# 20190505.net
KiCad netlist of a schematic drawn in EAGLE
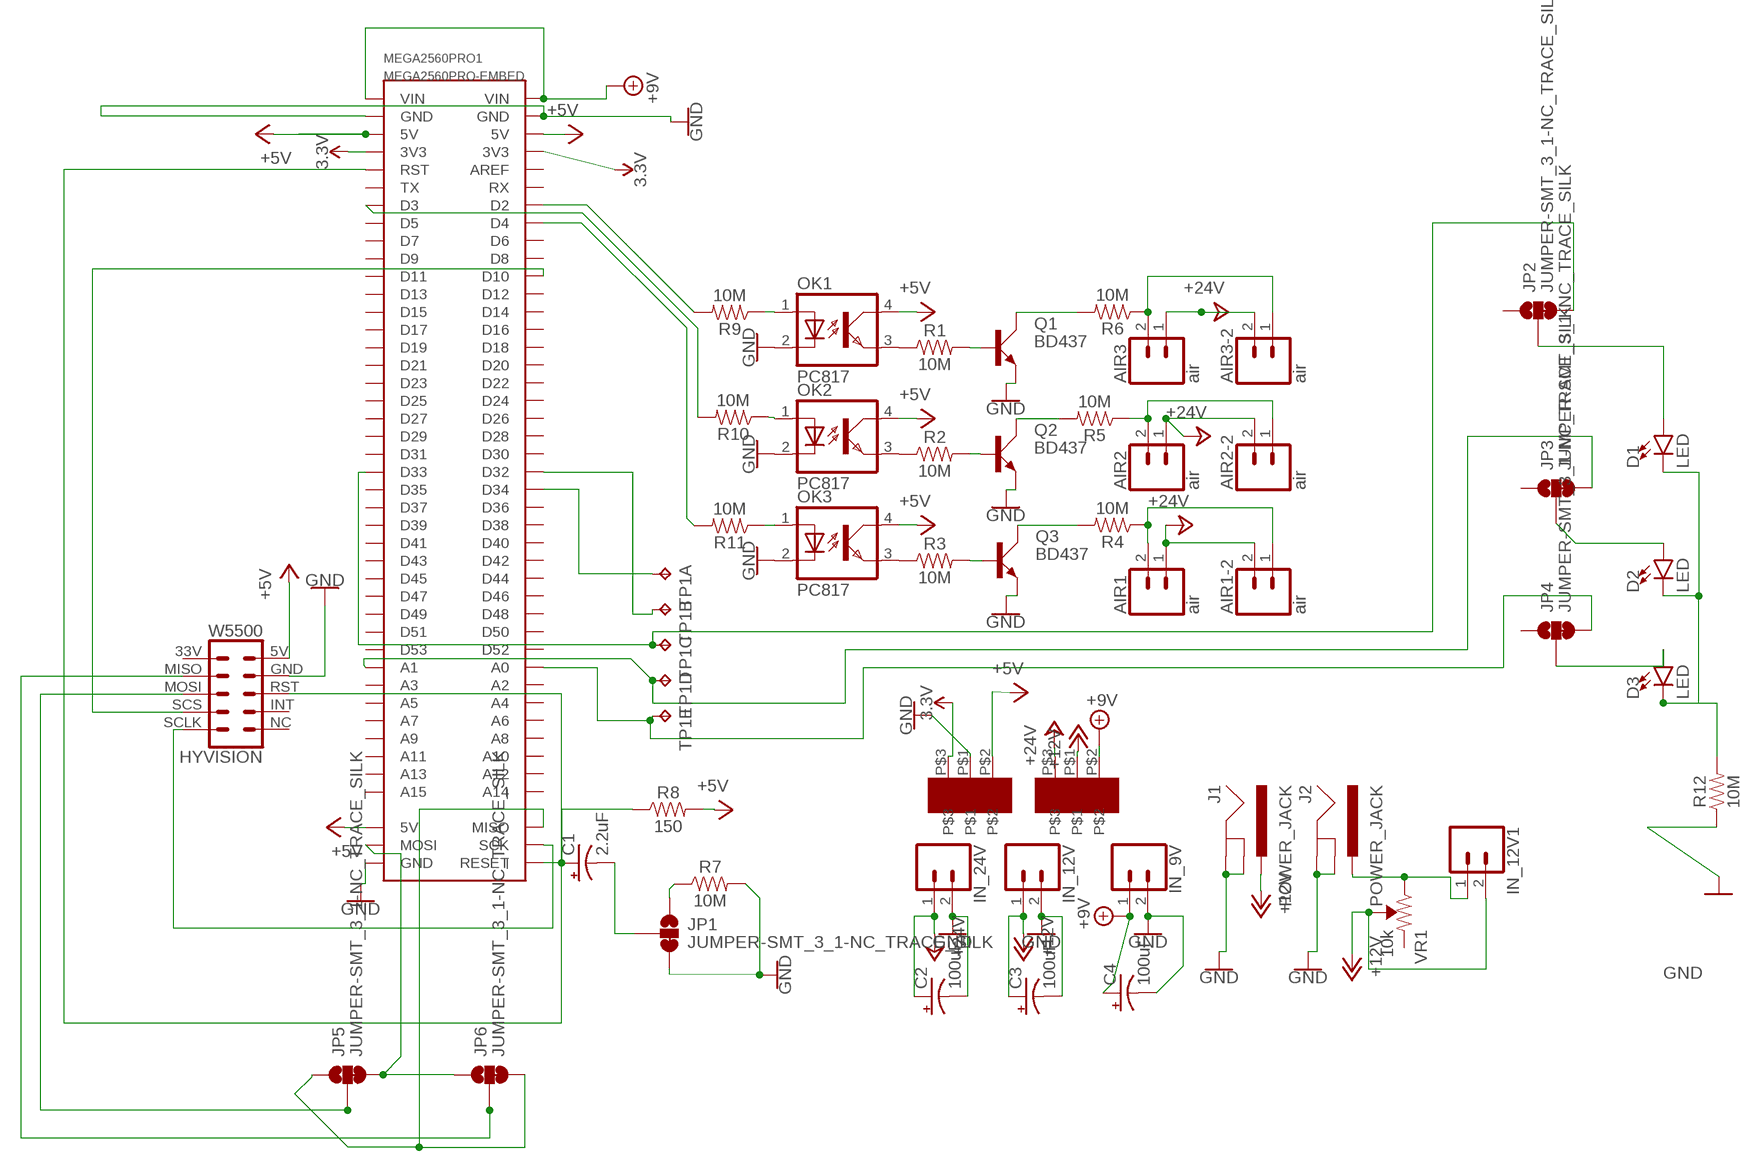
[diagram p0: schematic, sheet 1]

(export (version "E")
  (design (tool "Eeschema 10.0.6"))
  (components
    (comp (ref "AIR1")
      (value "air")
      (footprint "eagle-import:MOLEX-1X2_LOCK")
      (libsource (lib "eagle-import") (part "CONN_02POLAR_LOCK"))
    )
    (comp (ref "AIR1-2")
      (value "air")
      (footprint "eagle-import:1X02")
      (libsource (lib "eagle-import") (part "CONN_02"))
    )
    (comp (ref "AIR2")
      (value "air")
      (footprint "eagle-import:MOLEX-1X2_LOCK")
      (libsource (lib "eagle-import") (part "CONN_02POLAR_LOCK"))
    )
    (comp (ref "AIR2-2")
      (value "air")
      (footprint "eagle-import:1X02")
      (libsource (lib "eagle-import") (part "CONN_02"))
    )
    (comp (ref "AIR3")
      (value "air")
      (footprint "eagle-import:MOLEX-1X2_LOCK")
      (libsource (lib "eagle-import") (part "CONN_02POLAR_LOCK"))
    )
    (comp (ref "AIR3-2")
      (value "air")
      (footprint "eagle-import:1X02")
      (libsource (lib "eagle-import") (part "CONN_02"))
    )
    (comp (ref "C1")
      (value "2.2uF")
      (footprint "eagle-import:CPOL-RADIAL-2.5MM-5MM-KIT")
      (libsource (lib "eagle-import") (part "10UF-POLAR-RADIAL-2.5MM-KIT-25V-20%"))
    )
    (comp (ref "C2")
      (value "100uF")
      (footprint "eagle-import:CPOL-RADIAL-2.5MM-6.5MM")
      (libsource (lib "eagle-import") (part "100UF-POLAR-RADIAL-2.5MM-25V-20%"))
    )
    (comp (ref "C3")
      (value "100uF")
      (footprint "eagle-import:CPOL-RADIAL-2.5MM-6.5MM")
      (libsource (lib "eagle-import") (part "100UF-POLAR-RADIAL-2.5MM-25V-20%"))
    )
    (comp (ref "C4")
      (value "100uF")
      (footprint "eagle-import:CPOL-RADIAL-2.5MM-6.5MM")
      (libsource (lib "eagle-import") (part "100UF-POLAR-RADIAL-2.5MM-25V-20%"))
    )
    (comp (ref "D1")
      (value "LED")
      (footprint "eagle-import:LED_5MM")
      (libsource (lib "eagle-import") (part "LED5MM"))
    )
    (comp (ref "D2")
      (value "LED")
      (footprint "eagle-import:LED_5MM")
      (libsource (lib "eagle-import") (part "LED5MM"))
    )
    (comp (ref "D3")
      (value "LED")
      (footprint "eagle-import:LED_5MM")
      (libsource (lib "eagle-import") (part "LED5MM"))
    )
    (comp (ref "HYVISION")
      (value "W5500")
      (footprint "eagle-import:W5500")
      (libsource (lib "eagle-import") (part "W5500"))
    )
    (comp (ref "IN_9V")
      (value "CONN_02POLAR_LOCK")
      (footprint "eagle-import:MOLEX-1X2_LOCK")
      (libsource (lib "eagle-import") (part "CONN_02POLAR_LOCK"))
    )
    (comp (ref "IN_12V")
      (value "CONN_02POLAR_LOCK")
      (footprint "eagle-import:MOLEX-1X2_LOCK")
      (libsource (lib "eagle-import") (part "CONN_02POLAR_LOCK"))
    )
    (comp (ref "IN_12V1")
      (value "CONN_02POLAR_LOCK")
      (footprint "eagle-import:MOLEX-1X2_LOCK")
      (libsource (lib "eagle-import") (part "CONN_02POLAR_LOCK"))
    )
    (comp (ref "IN_24V")
      (value "CONN_02POLAR_LOCK")
      (footprint "eagle-import:MOLEX-1X2_LOCK")
      (libsource (lib "eagle-import") (part "CONN_02POLAR_LOCK"))
    )
    (comp (ref "J1")
      (value "POWER_JACK")
      (footprint "eagle-import:POWER_JACK_PTH")
      (libsource (lib "eagle-import") (part "POWER_JACK"))
    )
    (comp (ref "J2")
      (value "POWER_JACK")
      (footprint "eagle-import:POWER_JACK_PTH")
      (libsource (lib "eagle-import") (part "POWER_JACK"))
    )
    (comp (ref "JP1")
      (value "JUMPER-SMT_3_1-NC_TRACE_SILK")
      (footprint "eagle-import:SMT-JUMPER_3_1-NC_TRACE_SILK")
      (libsource (lib "eagle-import") (part "JUMPER-SMT_3_1-NC_TRACE_SILK"))
    )
    (comp (ref "JP2")
      (value "JUMPER-SMT_3_1-NC_TRACE_SILK")
      (footprint "eagle-import:SMT-JUMPER_3_1-NC_TRACE_SILK")
      (libsource (lib "eagle-import") (part "JUMPER-SMT_3_1-NC_TRACE_SILK"))
    )
    (comp (ref "JP3")
      (value "JUMPER-SMT_3_1-NC_TRACE_SILK")
      (footprint "eagle-import:SMT-JUMPER_3_1-NC_TRACE_SILK")
      (libsource (lib "eagle-import") (part "JUMPER-SMT_3_1-NC_TRACE_SILK"))
    )
    (comp (ref "JP4")
      (value "JUMPER-SMT_3_1-NC_TRACE_SILK")
      (footprint "eagle-import:SMT-JUMPER_3_1-NC_TRACE_SILK")
      (libsource (lib "eagle-import") (part "JUMPER-SMT_3_1-NC_TRACE_SILK"))
    )
    (comp (ref "JP5")
      (value "JUMPER-SMT_3_1-NC_TRACE_SILK")
      (footprint "eagle-import:SMT-JUMPER_3_1-NC_TRACE_SILK")
      (libsource (lib "eagle-import") (part "JUMPER-SMT_3_1-NC_TRACE_SILK"))
    )
    (comp (ref "JP6")
      (value "JUMPER-SMT_3_1-NC_TRACE_SILK")
      (footprint "eagle-import:SMT-JUMPER_3_1-NC_TRACE_SILK")
      (libsource (lib "eagle-import") (part "JUMPER-SMT_3_1-NC_TRACE_SILK"))
    )
    (comp (ref "MEGA2560PRO1")
      (value "MEGA2560PRO-EMBED")
      (footprint "eagle-import:MEGA2560PRO-EMBED")
      (libsource (lib "eagle-import") (part "MEGA2560PRO-EMBED"))
    )
    (comp (ref "OK1")
      (value "PC817")
      (footprint "eagle-import:DIL04")
      (fields (field (name "MPN") "PC817X4J000F"))
      (libsource (lib "eagle-import") (part "PC817"))
    )
    (comp (ref "OK2")
      (value "PC817")
      (footprint "eagle-import:DIL04")
      (fields (field (name "MPN") "PC817X4J000F"))
      (libsource (lib "eagle-import") (part "PC817"))
    )
    (comp (ref "OK3")
      (value "PC817")
      (footprint "eagle-import:DIL04")
      (fields (field (name "MPN") "PC817X4J000F"))
      (libsource (lib "eagle-import") (part "PC817"))
    )
    (comp (ref "Q1")
      (value "BD437")
      (footprint "eagle-import:TO126AV")
      (libsource (lib "eagle-import") (part "BD437"))
    )
    (comp (ref "Q2")
      (value "BD437")
      (footprint "eagle-import:TO126AV")
      (libsource (lib "eagle-import") (part "BD437"))
    )
    (comp (ref "Q3")
      (value "BD437")
      (footprint "eagle-import:TO126AV")
      (libsource (lib "eagle-import") (part "BD437"))
    )
    (comp (ref "R1")
      (value "10M")
      (footprint "eagle-import:AXIAL-0.3")
      (libsource (lib "eagle-import") (part "10MOHM-HORIZ-1/4W-5%"))
    )
    (comp (ref "R2")
      (value "10M")
      (footprint "eagle-import:AXIAL-0.3")
      (libsource (lib "eagle-import") (part "10MOHM-HORIZ-1/4W-5%"))
    )
    (comp (ref "R3")
      (value "10M")
      (footprint "eagle-import:AXIAL-0.3")
      (libsource (lib "eagle-import") (part "10MOHM-HORIZ-1/4W-5%"))
    )
    (comp (ref "R4")
      (value "10M")
      (footprint "eagle-import:AXIAL-0.3")
      (libsource (lib "eagle-import") (part "10MOHM-HORIZ-1/4W-5%"))
    )
    (comp (ref "R5")
      (value "10M")
      (footprint "eagle-import:AXIAL-0.3")
      (libsource (lib "eagle-import") (part "10MOHM-HORIZ-1/4W-5%"))
    )
    (comp (ref "R6")
      (value "10M")
      (footprint "eagle-import:AXIAL-0.3")
      (libsource (lib "eagle-import") (part "10MOHM-HORIZ-1/4W-5%"))
    )
    (comp (ref "R7")
      (value "10M")
      (footprint "eagle-import:AXIAL-0.3")
      (libsource (lib "eagle-import") (part "10MOHM-HORIZ-1/4W-5%"))
    )
    (comp (ref "R8")
      (value "150")
      (footprint "eagle-import:AXIAL-0.3")
      (libsource (lib "eagle-import") (part "10MOHM-HORIZ-1/4W-5%"))
    )
    (comp (ref "R9")
      (value "10M")
      (footprint "eagle-import:AXIAL-0.3")
      (libsource (lib "eagle-import") (part "10MOHM-HORIZ-1/4W-5%"))
    )
    (comp (ref "R10")
      (value "10M")
      (footprint "eagle-import:AXIAL-0.3")
      (libsource (lib "eagle-import") (part "10MOHM-HORIZ-1/4W-5%"))
    )
    (comp (ref "R11")
      (value "10M")
      (footprint "eagle-import:AXIAL-0.3")
      (libsource (lib "eagle-import") (part "10MOHM-HORIZ-1/4W-5%"))
    )
    (comp (ref "R12")
      (value "10M")
      (footprint "eagle-import:AXIAL-0.3")
      (libsource (lib "eagle-import") (part "10MOHM-HORIZ-1/4W-5%"))
    )
    (comp (ref "TP1")
      (value "TP5P5-25-13")
      (footprint "eagle-import:P5-25-13")
      (libsource (lib "eagle-import") (part "TP5P5-25-13"))
    )
    (comp (ref "U$2")
      (value "AC_3PINAC3PIN7MM")
      (footprint "eagle-import:AC3PIN7MM")
      (libsource (lib "eagle-import") (part "AC_3PINAC3PIN7MM"))
    )
    (comp (ref "U$4")
      (value "AC_3PINAC3PIN7MM")
      (footprint "eagle-import:AC3PIN7MM")
      (libsource (lib "eagle-import") (part "AC_3PINAC3PIN7MM"))
    )
    (comp (ref "VR1")
      (value "10k")
      (footprint "eagle-import:TRIMPOT-PTH-3386U")
      (libsource (lib "eagle-import") (part "TRIMPOT-PTH-10MM-KNOB-1/2W-10%"))
    )
  )
  (nets
    (net (code "1") (name "+5V") (class "Default")
      (node (ref "HYVISION") (pin "5V") (pinfunction "5V_5V") (pintype "passive"))
      (node (ref "MEGA2560PRO1") (pin "5V@1") (pinfunction "5V_5V@1") (pintype "bidirectional"))
      (node (ref "MEGA2560PRO1") (pin "5V@2") (pinfunction "5V_5V@2") (pintype "bidirectional"))
      (node (ref "MEGA2560PRO1") (pin "5V@3") (pinfunction "5V_5V@3") (pintype "bidirectional"))
      (node (ref "OK1") (pin "4") (pinfunction "COL_4") (pintype "passive"))
      (node (ref "OK2") (pin "4") (pinfunction "COL_4") (pintype "passive"))
      (node (ref "OK3") (pin "4") (pinfunction "COL_4") (pintype "passive"))
      (node (ref "R8") (pin "P$2") (pinfunction "2_P$2") (pintype "passive"))
      (node (ref "U$4") (pin "P$2") (pinfunction "P$2_P$2") (pintype "bidirectional"))
    )
    (net (code "2") (name "+9V") (class "Default")
      (node (ref "C4") (pin "1") (pinfunction "+_1") (pintype "passive"))
      (node (ref "IN_9V") (pin "1") (pinfunction "1_1") (pintype "passive"))
      (node (ref "MEGA2560PRO1") (pin "VIN@1") (pinfunction "VIN_VIN@1") (pintype "bidirectional"))
      (node (ref "MEGA2560PRO1") (pin "VIN@2") (pinfunction "VIN_VIN@2") (pintype "bidirectional"))
      (node (ref "U$2") (pin "P$2") (pinfunction "P$2_P$2") (pintype "bidirectional"))
    )
    (net (code "3") (name "+12V") (class "Default")
      (node (ref "C3") (pin "1") (pinfunction "+_1") (pintype "passive"))
      (node (ref "IN_12V") (pin "1") (pinfunction "1_1") (pintype "passive"))
      (node (ref "IN_12V1") (pin "2") (pinfunction "2_2") (pintype "passive"))
      (node (ref "J1") (pin "PWR") (pinfunction "PWR_PWR") (pintype "bidirectional"))
      (node (ref "U$2") (pin "P$1") (pinfunction "P$1_P$1") (pintype "bidirectional"))
      (node (ref "VR1") (pin "2") (pinfunction "WIPER_2") (pintype "passive"))
    )
    (net (code "4") (name "+24V") (class "Default")
      (node (ref "AIR1") (pin "1") (pinfunction "1_1") (pintype "passive"))
      (node (ref "AIR1-2") (pin "2") (pinfunction "2_2") (pintype "passive"))
      (node (ref "AIR2") (pin "1") (pinfunction "1_1") (pintype "passive"))
      (node (ref "AIR2-2") (pin "2") (pinfunction "2_2") (pintype "passive"))
      (node (ref "AIR3") (pin "1") (pinfunction "1_1") (pintype "passive"))
      (node (ref "AIR3-2") (pin "2") (pinfunction "2_2") (pintype "passive"))
      (node (ref "C2") (pin "1") (pinfunction "+_1") (pintype "passive"))
      (node (ref "IN_24V") (pin "1") (pinfunction "1_1") (pintype "passive"))
      (node (ref "U$2") (pin "P$3") (pinfunction "P$3_P$3") (pintype "bidirectional"))
    )
    (net (code "5") (name "3.3V") (class "Default")
      (node (ref "MEGA2560PRO1") (pin "3V3@1") (pinfunction "3V3_3V3@1") (pintype "bidirectional"))
      (node (ref "MEGA2560PRO1") (pin "3V3@2") (pinfunction "3V3_3V3@2") (pintype "bidirectional"))
      (node (ref "U$4") (pin "P$3") (pinfunction "P$3_P$3") (pintype "bidirectional"))
    )
    (net (code "6") (name "GND") (class "Default")
      (node (ref "C2") (pin "2") (pinfunction "-_2") (pintype "passive"))
      (node (ref "C3") (pin "2") (pinfunction "-_2") (pintype "passive"))
      (node (ref "C4") (pin "2") (pinfunction "-_2") (pintype "passive"))
      (node (ref "HYVISION") (pin "GND") (pinfunction "GND_GND") (pintype "passive"))
      (node (ref "IN_12V") (pin "2") (pinfunction "2_2") (pintype "passive"))
      (node (ref "IN_24V") (pin "2") (pinfunction "2_2") (pintype "passive"))
      (node (ref "IN_9V") (pin "2") (pinfunction "2_2") (pintype "passive"))
      (node (ref "J1") (pin "GND") (pinfunction "GND_GND") (pintype "bidirectional"))
      (node (ref "J1") (pin "GNDBREAK") (pinfunction "GNDBREAK_GNDBREAK") (pintype "bidirectional"))
      (node (ref "J2") (pin "GND") (pinfunction "GND_GND") (pintype "bidirectional"))
      (node (ref "J2") (pin "GNDBREAK") (pinfunction "GNDBREAK_GNDBREAK") (pintype "bidirectional"))
      (node (ref "JP1") (pin "3") (pinfunction "3_3") (pintype "passive"))
      (node (ref "MEGA2560PRO1") (pin "GND@1") (pinfunction "GND_GND@1") (pintype "bidirectional"))
      (node (ref "MEGA2560PRO1") (pin "GND@2") (pinfunction "GND_GND@2") (pintype "bidirectional"))
      (node (ref "MEGA2560PRO1") (pin "GND@3") (pinfunction "GND_GND@3") (pintype "bidirectional"))
      (node (ref "OK1") (pin "2") (pinfunction "C_2") (pintype "passive"))
      (node (ref "OK2") (pin "2") (pinfunction "C_2") (pintype "passive"))
      (node (ref "OK3") (pin "2") (pinfunction "C_2") (pintype "passive"))
      (node (ref "Q1") (pin "E") (pinfunction "E_E") (pintype "passive"))
      (node (ref "Q2") (pin "E") (pinfunction "E_E") (pintype "passive"))
      (node (ref "Q3") (pin "E") (pinfunction "E_E") (pintype "passive"))
      (node (ref "R12") (pin "P$1") (pinfunction "1_P$1") (pintype "passive"))
      (node (ref "R7") (pin "P$2") (pinfunction "2_P$2") (pintype "passive"))
      (node (ref "U$4") (pin "P$1") (pinfunction "P$1_P$1") (pintype "bidirectional"))
    )
    (net (code "7") (name "Net-(C1-+)") (class "Default")
      (node (ref "C1") (pin "1") (pinfunction "+_1") (pintype "passive"))
      (node (ref "HYVISION") (pin "RST") (pinfunction "RST_RST") (pintype "passive"))
      (node (ref "MEGA2560PRO1") (pin "RESET") (pinfunction "RESET_RESET") (pintype "bidirectional"))
      (node (ref "MEGA2560PRO1") (pin "RST") (pinfunction "RST_RST") (pintype "bidirectional"))
      (node (ref "R8") (pin "P$1") (pinfunction "1_P$1") (pintype "passive"))
    )
    (net (code "8") (name "Net-(C1--)") (class "Default")
      (node (ref "C1") (pin "2") (pinfunction "-_2") (pintype "passive"))
      (node (ref "JP1") (pin "2") (pinfunction "2_2") (pintype "passive"))
    )
    (net (code "9") (name "Net-(D1-C)") (class "Default")
      (node (ref "D1") (pin "K") (pinfunction "C_K") (pintype "passive"))
      (node (ref "D2") (pin "K") (pinfunction "C_K") (pintype "passive"))
      (node (ref "D3") (pin "K") (pinfunction "C_K") (pintype "passive"))
      (node (ref "R12") (pin "P$2") (pinfunction "2_P$2") (pintype "passive"))
    )
    (net (code "10") (name "Net-(D1-PadA)") (class "Default")
      (node (ref "D1") (pin "A") (pinfunction "A_A") (pintype "passive"))
      (node (ref "JP2") (pin "2") (pinfunction "2_2") (pintype "passive"))
    )
    (net (code "11") (name "Net-(D2-PadA)") (class "Default")
      (node (ref "D2") (pin "A") (pinfunction "A_A") (pintype "passive"))
      (node (ref "JP3") (pin "2") (pinfunction "2_2") (pintype "passive"))
    )
    (net (code "12") (name "Net-(D3-PadA)") (class "Default")
      (node (ref "D3") (pin "A") (pinfunction "A_A") (pintype "passive"))
      (node (ref "JP4") (pin "2") (pinfunction "2_2") (pintype "passive"))
    )
    (net (code "13") (name "Net-(HYVISION-PadMISO)") (class "Default")
      (node (ref "HYVISION") (pin "MISO") (pinfunction "MISO_MISO") (pintype "passive"))
      (node (ref "JP6") (pin "2") (pinfunction "2_2") (pintype "passive"))
    )
    (net (code "14") (name "Net-(HYVISION-PadMOSI)") (class "Default")
      (node (ref "HYVISION") (pin "MOSI") (pinfunction "MOSI_MOSI") (pintype "passive"))
      (node (ref "JP5") (pin "2") (pinfunction "2_2") (pintype "passive"))
    )
    (net (code "15") (name "Net-(HYVISION-PadSCLK)") (class "Default")
      (node (ref "HYVISION") (pin "SCLK") (pinfunction "SCLK_SCLK") (pintype "passive"))
      (node (ref "MEGA2560PRO1") (pin "SCK") (pinfunction "SCK_SCK") (pintype "bidirectional"))
    )
    (net (code "16") (name "Net-(HYVISION-PadSCS)") (class "Default")
      (node (ref "HYVISION") (pin "SCS") (pinfunction "SCS_SCS") (pintype "passive"))
      (node (ref "MEGA2560PRO1") (pin "D10") (pinfunction "D10_D10") (pintype "bidirectional"))
    )
    (net (code "17") (name "Net-(JP5-Pad1)") (class "Default")
      (node (ref "JP5") (pin "1") (pinfunction "1_1") (pintype "passive"))
      (node (ref "JP6") (pin "3") (pinfunction "3_3") (pintype "passive"))
      (node (ref "MEGA2560PRO1") (pin "MISO") (pinfunction "MISO_MISO") (pintype "bidirectional"))
    )
    (net (code "18") (name "Net-(JP5-Pad3)") (class "Default")
      (node (ref "JP5") (pin "3") (pinfunction "3_3") (pintype "passive"))
      (node (ref "JP6") (pin "1") (pinfunction "1_1") (pintype "passive"))
      (node (ref "MEGA2560PRO1") (pin "MOSI") (pinfunction "MOSI_MOSI") (pintype "bidirectional"))
    )
    (net (code "19") (name "Net-(OK1-A)") (class "Default")
      (node (ref "OK1") (pin "1") (pinfunction "A_1") (pintype "passive"))
      (node (ref "R9") (pin "P$1") (pinfunction "1_P$1") (pintype "passive"))
    )
    (net (code "20") (name "Net-(OK1-EMIT)") (class "Default")
      (node (ref "OK1") (pin "3") (pinfunction "EMIT_3") (pintype "passive"))
      (node (ref "R1") (pin "P$1") (pinfunction "1_P$1") (pintype "passive"))
    )
    (net (code "21") (name "Net-(OK2-A)") (class "Default")
      (node (ref "OK2") (pin "1") (pinfunction "A_1") (pintype "passive"))
      (node (ref "R10") (pin "P$1") (pinfunction "1_P$1") (pintype "passive"))
    )
    (net (code "22") (name "Net-(OK2-EMIT)") (class "Default")
      (node (ref "OK2") (pin "3") (pinfunction "EMIT_3") (pintype "passive"))
      (node (ref "R2") (pin "P$1") (pinfunction "1_P$1") (pintype "passive"))
    )
    (net (code "23") (name "Net-(OK3-A)") (class "Default")
      (node (ref "OK3") (pin "1") (pinfunction "A_1") (pintype "passive"))
      (node (ref "R11") (pin "P$1") (pinfunction "1_P$1") (pintype "passive"))
    )
    (net (code "24") (name "Net-(OK3-EMIT)") (class "Default")
      (node (ref "OK3") (pin "3") (pinfunction "EMIT_3") (pintype "passive"))
      (node (ref "R3") (pin "P$1") (pinfunction "1_P$1") (pintype "passive"))
    )
    (net (code "25") (name "Net-(R1-2)") (class "Default")
      (node (ref "Q1") (pin "B") (pinfunction "B_B") (pintype "passive"))
      (node (ref "R1") (pin "P$2") (pinfunction "2_P$2") (pintype "passive"))
    )
    (net (code "26") (name "Net-(R2-2)") (class "Default")
      (node (ref "Q2") (pin "B") (pinfunction "B_B") (pintype "passive"))
      (node (ref "R2") (pin "P$2") (pinfunction "2_P$2") (pintype "passive"))
    )
    (net (code "27") (name "Net-(R3-2)") (class "Default")
      (node (ref "Q3") (pin "B") (pinfunction "B_B") (pintype "passive"))
      (node (ref "R3") (pin "P$2") (pinfunction "2_P$2") (pintype "passive"))
    )
    (net (code "28") (name "Net-(R4-1)") (class "Default")
      (node (ref "AIR1") (pin "2") (pinfunction "2_2") (pintype "passive"))
      (node (ref "AIR1-2") (pin "1") (pinfunction "1_1") (pintype "passive"))
      (node (ref "R4") (pin "P$1") (pinfunction "1_P$1") (pintype "passive"))
    )
    (net (code "29") (name "Net-(R4-2)") (class "Default")
      (node (ref "Q3") (pin "C") (pinfunction "C_C") (pintype "passive"))
      (node (ref "R4") (pin "P$2") (pinfunction "2_P$2") (pintype "passive"))
    )
    (net (code "30") (name "Net-(R5-1)") (class "Default")
      (node (ref "AIR2") (pin "2") (pinfunction "2_2") (pintype "passive"))
      (node (ref "AIR2-2") (pin "1") (pinfunction "1_1") (pintype "passive"))
      (node (ref "R5") (pin "P$1") (pinfunction "1_P$1") (pintype "passive"))
    )
    (net (code "31") (name "Net-(R5-2)") (class "Default")
      (node (ref "Q2") (pin "C") (pinfunction "C_C") (pintype "passive"))
      (node (ref "R5") (pin "P$2") (pinfunction "2_P$2") (pintype "passive"))
    )
    (net (code "32") (name "Net-(R6-1)") (class "Default")
      (node (ref "AIR3") (pin "2") (pinfunction "2_2") (pintype "passive"))
      (node (ref "AIR3-2") (pin "1") (pinfunction "1_1") (pintype "passive"))
      (node (ref "R6") (pin "P$1") (pinfunction "1_P$1") (pintype "passive"))
    )
    (net (code "33") (name "Net-(R6-2)") (class "Default")
      (node (ref "Q1") (pin "C") (pinfunction "C_C") (pintype "passive"))
      (node (ref "R6") (pin "P$2") (pinfunction "2_P$2") (pintype "passive"))
    )
    (net (code "34") (name "Net-(R7-1)") (class "Default")
      (node (ref "JP1") (pin "1") (pinfunction "1_1") (pintype "passive"))
      (node (ref "R7") (pin "P$1") (pinfunction "1_P$1") (pintype "passive"))
    )
    (net (code "35") (name "Net-(R9-2)") (class "Default")
      (node (ref "MEGA2560PRO1") (pin "D2") (pinfunction "D2_D2") (pintype "bidirectional"))
      (node (ref "R9") (pin "P$2") (pinfunction "2_P$2") (pintype "passive"))
    )
    (net (code "36") (name "Net-(R10-2)") (class "Default")
      (node (ref "MEGA2560PRO1") (pin "D3") (pinfunction "D3_D3") (pintype "bidirectional"))
      (node (ref "R10") (pin "P$2") (pinfunction "2_P$2") (pintype "passive"))
    )
    (net (code "37") (name "Net-(R11-2)") (class "Default")
      (node (ref "MEGA2560PRO1") (pin "D4") (pinfunction "D4_D4") (pintype "bidirectional"))
      (node (ref "R11") (pin "P$2") (pinfunction "2_P$2") (pintype "passive"))
    )
    (net (code "38") (name "Net-(TP1A-TP)") (class "Default")
      (node (ref "MEGA2560PRO1") (pin "D34") (pinfunction "D34_D34") (pintype "bidirectional"))
      (node (ref "TP1") (pin "TP-1") (pinfunction "TP_TP-1") (pintype "input"))
    )
    (net (code "39") (name "Net-(TP1B-TP)") (class "Default")
      (node (ref "MEGA2560PRO1") (pin "D32") (pinfunction "D32_D32") (pintype "bidirectional"))
      (node (ref "TP1") (pin "TP-2") (pinfunction "TP_TP-2") (pintype "input"))
    )
    (net (code "40") (name "Net-(TP1C-TP)") (class "Default")
      (node (ref "JP2") (pin "3") (pinfunction "3_3") (pintype "passive"))
      (node (ref "MEGA2560PRO1") (pin "D33") (pinfunction "D33_D33") (pintype "bidirectional"))
      (node (ref "TP1") (pin "TP-3") (pinfunction "TP_TP-3") (pintype "input"))
    )
    (net (code "41") (name "Net-(TP1D-TP)") (class "Default")
      (node (ref "JP3") (pin "3") (pinfunction "3_3") (pintype "passive"))
      (node (ref "MEGA2560PRO1") (pin "A1") (pinfunction "A1_A1") (pintype "bidirectional"))
      (node (ref "TP1") (pin "TP-4") (pinfunction "TP_TP-4") (pintype "input"))
    )
    (net (code "42") (name "Net-(TP1E-TP)") (class "Default")
      (node (ref "JP4") (pin "3") (pinfunction "3_3") (pintype "passive"))
      (node (ref "MEGA2560PRO1") (pin "A0") (pinfunction "A0_A0") (pintype "bidirectional"))
      (node (ref "TP1") (pin "TP-5") (pinfunction "TP_TP-5") (pintype "input"))
    )
    (net (code "43") (name "Net-(VR1-CW)") (class "Default")
      (node (ref "IN_12V1") (pin "1") (pinfunction "1_1") (pintype "passive"))
      (node (ref "J2") (pin "PWR") (pinfunction "PWR_PWR") (pintype "bidirectional"))
      (node (ref "VR1") (pin "3") (pinfunction "CW_3") (pintype "passive"))
    )
    (net (code "44") (name "unconnected-(HYVISION-3V3-Pad33V)") (class "Default")
      (node (ref "HYVISION") (pin "33V") (pinfunction "3V3_33V") (pintype "passive"))
    )
    (net (code "45") (name "unconnected-(HYVISION-PadINT)") (class "Default")
      (node (ref "HYVISION") (pin "INT") (pinfunction "INT_INT") (pintype "passive"))
    )
    (net (code "46") (name "unconnected-(HYVISION-PadNC)") (class "Default")
      (node (ref "HYVISION") (pin "NC") (pinfunction "NC_NC") (pintype "passive"))
    )
    (net (code "47") (name "unconnected-(JP2-Pad1)") (class "Default")
      (node (ref "JP2") (pin "1") (pinfunction "1_1") (pintype "passive"))
    )
    (net (code "48") (name "unconnected-(JP3-Pad1)") (class "Default")
      (node (ref "JP3") (pin "1") (pinfunction "1_1") (pintype "passive"))
    )
    (net (code "49") (name "unconnected-(JP4-Pad1)") (class "Default")
      (node (ref "JP4") (pin "1") (pinfunction "1_1") (pintype "passive"))
    )
    (net (code "50") (name "unconnected-(MEGA2560PRO1-PadA2)") (class "Default")
      (node (ref "MEGA2560PRO1") (pin "A2") (pinfunction "A2_A2") (pintype "bidirectional"))
    )
    (net (code "51") (name "unconnected-(MEGA2560PRO1-PadA3)") (class "Default")
      (node (ref "MEGA2560PRO1") (pin "A3") (pinfunction "A3_A3") (pintype "bidirectional"))
    )
    (net (code "52") (name "unconnected-(MEGA2560PRO1-PadA4)") (class "Default")
      (node (ref "MEGA2560PRO1") (pin "A4") (pinfunction "A4_A4") (pintype "bidirectional"))
    )
    (net (code "53") (name "unconnected-(MEGA2560PRO1-PadA5)") (class "Default")
      (node (ref "MEGA2560PRO1") (pin "A5") (pinfunction "A5_A5") (pintype "bidirectional"))
    )
    (net (code "54") (name "unconnected-(MEGA2560PRO1-PadA6)") (class "Default")
      (node (ref "MEGA2560PRO1") (pin "A6") (pinfunction "A6_A6") (pintype "bidirectional"))
    )
    (net (code "55") (name "unconnected-(MEGA2560PRO1-PadA7)") (class "Default")
      (node (ref "MEGA2560PRO1") (pin "A7") (pinfunction "A7_A7") (pintype "bidirectional"))
    )
    (net (code "56") (name "unconnected-(MEGA2560PRO1-PadA8)") (class "Default")
      (node (ref "MEGA2560PRO1") (pin "A8") (pinfunction "A8_A8") (pintype "bidirectional"))
    )
    (net (code "57") (name "unconnected-(MEGA2560PRO1-PadA9)") (class "Default")
      (node (ref "MEGA2560PRO1") (pin "A9") (pinfunction "A9_A9") (pintype "bidirectional"))
    )
    (net (code "58") (name "unconnected-(MEGA2560PRO1-PadA10)") (class "Default")
      (node (ref "MEGA2560PRO1") (pin "A10") (pinfunction "A10_A10") (pintype "bidirectional"))
    )
    (net (code "59") (name "unconnected-(MEGA2560PRO1-PadA11)") (class "Default")
      (node (ref "MEGA2560PRO1") (pin "A11") (pinfunction "A11_A11") (pintype "bidirectional"))
    )
    (net (code "60") (name "unconnected-(MEGA2560PRO1-PadA12)") (class "Default")
      (node (ref "MEGA2560PRO1") (pin "A12") (pinfunction "A12_A12") (pintype "bidirectional"))
    )
    (net (code "61") (name "unconnected-(MEGA2560PRO1-PadA13)") (class "Default")
      (node (ref "MEGA2560PRO1") (pin "A13") (pinfunction "A13_A13") (pintype "bidirectional"))
    )
    (net (code "62") (name "unconnected-(MEGA2560PRO1-PadA14)") (class "Default")
      (node (ref "MEGA2560PRO1") (pin "A14") (pinfunction "A14_A14") (pintype "bidirectional"))
    )
    (net (code "63") (name "unconnected-(MEGA2560PRO1-PadA15)") (class "Default")
      (node (ref "MEGA2560PRO1") (pin "A15") (pinfunction "A15_A15") (pintype "bidirectional"))
    )
    (net (code "64") (name "unconnected-(MEGA2560PRO1-PadAREF)") (class "Default")
      (node (ref "MEGA2560PRO1") (pin "AREF") (pinfunction "AREF_AREF") (pintype "bidirectional"))
    )
    (net (code "65") (name "unconnected-(MEGA2560PRO1-PadD5)") (class "Default")
      (node (ref "MEGA2560PRO1") (pin "D5") (pinfunction "D5_D5") (pintype "bidirectional"))
    )
    (net (code "66") (name "unconnected-(MEGA2560PRO1-PadD6)") (class "Default")
      (node (ref "MEGA2560PRO1") (pin "D6") (pinfunction "D6_D6") (pintype "bidirectional"))
    )
    (net (code "67") (name "unconnected-(MEGA2560PRO1-PadD7)") (class "Default")
      (node (ref "MEGA2560PRO1") (pin "D7") (pinfunction "D7_D7") (pintype "bidirectional"))
    )
    (net (code "68") (name "unconnected-(MEGA2560PRO1-PadD8)") (class "Default")
      (node (ref "MEGA2560PRO1") (pin "D8") (pinfunction "D8_D8") (pintype "bidirectional"))
    )
    (net (code "69") (name "unconnected-(MEGA2560PRO1-PadD9)") (class "Default")
      (node (ref "MEGA2560PRO1") (pin "D9") (pinfunction "D9_D9") (pintype "bidirectional"))
    )
    (net (code "70") (name "unconnected-(MEGA2560PRO1-PadD11)") (class "Default")
      (node (ref "MEGA2560PRO1") (pin "D11") (pinfunction "D11_D11") (pintype "bidirectional"))
    )
    (net (code "71") (name "unconnected-(MEGA2560PRO1-PadD12)") (class "Default")
      (node (ref "MEGA2560PRO1") (pin "D12") (pinfunction "D12_D12") (pintype "bidirectional"))
    )
    (net (code "72") (name "unconnected-(MEGA2560PRO1-PadD13)") (class "Default")
      (node (ref "MEGA2560PRO1") (pin "D13") (pinfunction "D13_D13") (pintype "bidirectional"))
    )
    (net (code "73") (name "unconnected-(MEGA2560PRO1-PadD14)") (class "Default")
      (node (ref "MEGA2560PRO1") (pin "D14") (pinfunction "D14_D14") (pintype "bidirectional"))
    )
    (net (code "74") (name "unconnected-(MEGA2560PRO1-PadD15)") (class "Default")
      (node (ref "MEGA2560PRO1") (pin "D15") (pinfunction "D15_D15") (pintype "bidirectional"))
    )
    (net (code "75") (name "unconnected-(MEGA2560PRO1-PadD16)") (class "Default")
      (node (ref "MEGA2560PRO1") (pin "D16") (pinfunction "D16_D16") (pintype "bidirectional"))
    )
    (net (code "76") (name "unconnected-(MEGA2560PRO1-PadD17)") (class "Default")
      (node (ref "MEGA2560PRO1") (pin "D17") (pinfunction "D17_D17") (pintype "bidirectional"))
    )
    (net (code "77") (name "unconnected-(MEGA2560PRO1-PadD18)") (class "Default")
      (node (ref "MEGA2560PRO1") (pin "D18") (pinfunction "D18_D18") (pintype "bidirectional"))
    )
    (net (code "78") (name "unconnected-(MEGA2560PRO1-PadD19)") (class "Default")
      (node (ref "MEGA2560PRO1") (pin "D19") (pinfunction "D19_D19") (pintype "bidirectional"))
    )
    (net (code "79") (name "unconnected-(MEGA2560PRO1-PadD20)") (class "Default")
      (node (ref "MEGA2560PRO1") (pin "D20") (pinfunction "D20_D20") (pintype "bidirectional"))
    )
    (net (code "80") (name "unconnected-(MEGA2560PRO1-PadD21)") (class "Default")
      (node (ref "MEGA2560PRO1") (pin "D21") (pinfunction "D21_D21") (pintype "bidirectional"))
    )
    (net (code "81") (name "unconnected-(MEGA2560PRO1-PadD22)") (class "Default")
      (node (ref "MEGA2560PRO1") (pin "D22") (pinfunction "D22_D22") (pintype "bidirectional"))
    )
    (net (code "82") (name "unconnected-(MEGA2560PRO1-PadD23)") (class "Default")
      (node (ref "MEGA2560PRO1") (pin "D23") (pinfunction "D23_D23") (pintype "bidirectional"))
    )
    (net (code "83") (name "unconnected-(MEGA2560PRO1-PadD24)") (class "Default")
      (node (ref "MEGA2560PRO1") (pin "D24") (pinfunction "D24_D24") (pintype "bidirectional"))
    )
    (net (code "84") (name "unconnected-(MEGA2560PRO1-PadD25)") (class "Default")
      (node (ref "MEGA2560PRO1") (pin "D25") (pinfunction "D25_D25") (pintype "bidirectional"))
    )
    (net (code "85") (name "unconnected-(MEGA2560PRO1-PadD26)") (class "Default")
      (node (ref "MEGA2560PRO1") (pin "D26") (pinfunction "D26_D26") (pintype "bidirectional"))
    )
    (net (code "86") (name "unconnected-(MEGA2560PRO1-PadD27)") (class "Default")
      (node (ref "MEGA2560PRO1") (pin "D27") (pinfunction "D27_D27") (pintype "bidirectional"))
    )
    (net (code "87") (name "unconnected-(MEGA2560PRO1-PadD28)") (class "Default")
      (node (ref "MEGA2560PRO1") (pin "D28") (pinfunction "D28_D28") (pintype "bidirectional"))
    )
    (net (code "88") (name "unconnected-(MEGA2560PRO1-PadD29)") (class "Default")
      (node (ref "MEGA2560PRO1") (pin "D29") (pinfunction "D29_D29") (pintype "bidirectional"))
    )
    (net (code "89") (name "unconnected-(MEGA2560PRO1-PadD30)") (class "Default")
      (node (ref "MEGA2560PRO1") (pin "D30") (pinfunction "D30_D30") (pintype "bidirectional"))
    )
    (net (code "90") (name "unconnected-(MEGA2560PRO1-PadD31)") (class "Default")
      (node (ref "MEGA2560PRO1") (pin "D31") (pinfunction "D31_D31") (pintype "bidirectional"))
    )
    (net (code "91") (name "unconnected-(MEGA2560PRO1-PadD35)") (class "Default")
      (node (ref "MEGA2560PRO1") (pin "D35") (pinfunction "D35_D35") (pintype "bidirectional"))
    )
    (net (code "92") (name "unconnected-(MEGA2560PRO1-PadD36)") (class "Default")
      (node (ref "MEGA2560PRO1") (pin "D36") (pinfunction "D36_D36") (pintype "bidirectional"))
    )
    (net (code "93") (name "unconnected-(MEGA2560PRO1-PadD37)") (class "Default")
      (node (ref "MEGA2560PRO1") (pin "D37") (pinfunction "D37_D37") (pintype "bidirectional"))
    )
    (net (code "94") (name "unconnected-(MEGA2560PRO1-PadD38)") (class "Default")
      (node (ref "MEGA2560PRO1") (pin "D38") (pinfunction "D38_D38") (pintype "bidirectional"))
    )
    (net (code "95") (name "unconnected-(MEGA2560PRO1-PadD39)") (class "Default")
      (node (ref "MEGA2560PRO1") (pin "D39") (pinfunction "D39_D39") (pintype "bidirectional"))
    )
    (net (code "96") (name "unconnected-(MEGA2560PRO1-PadD40)") (class "Default")
      (node (ref "MEGA2560PRO1") (pin "D40") (pinfunction "D40_D40") (pintype "bidirectional"))
    )
    (net (code "97") (name "unconnected-(MEGA2560PRO1-PadD41)") (class "Default")
      (node (ref "MEGA2560PRO1") (pin "D41") (pinfunction "D41_D41") (pintype "bidirectional"))
    )
    (net (code "98") (name "unconnected-(MEGA2560PRO1-PadD42)") (class "Default")
      (node (ref "MEGA2560PRO1") (pin "D42") (pinfunction "D42_D42") (pintype "bidirectional"))
    )
    (net (code "99") (name "unconnected-(MEGA2560PRO1-PadD43)") (class "Default")
      (node (ref "MEGA2560PRO1") (pin "D43") (pinfunction "D43_D43") (pintype "bidirectional"))
    )
    (net (code "100") (name "unconnected-(MEGA2560PRO1-PadD44)") (class "Default")
      (node (ref "MEGA2560PRO1") (pin "D44") (pinfunction "D44_D44") (pintype "bidirectional"))
    )
    (net (code "101") (name "unconnected-(MEGA2560PRO1-PadD45)") (class "Default")
      (node (ref "MEGA2560PRO1") (pin "D45") (pinfunction "D45_D45") (pintype "bidirectional"))
    )
    (net (code "102") (name "unconnected-(MEGA2560PRO1-PadD46)") (class "Default")
      (node (ref "MEGA2560PRO1") (pin "D46") (pinfunction "D46_D46") (pintype "bidirectional"))
    )
    (net (code "103") (name "unconnected-(MEGA2560PRO1-PadD47)") (class "Default")
      (node (ref "MEGA2560PRO1") (pin "D47") (pinfunction "D47_D47") (pintype "bidirectional"))
    )
    (net (code "104") (name "unconnected-(MEGA2560PRO1-PadD48)") (class "Default")
      (node (ref "MEGA2560PRO1") (pin "D48") (pinfunction "D48_D48") (pintype "bidirectional"))
    )
    (net (code "105") (name "unconnected-(MEGA2560PRO1-PadD49)") (class "Default")
      (node (ref "MEGA2560PRO1") (pin "D49") (pinfunction "D49_D49") (pintype "bidirectional"))
    )
    (net (code "106") (name "unconnected-(MEGA2560PRO1-PadD50)") (class "Default")
      (node (ref "MEGA2560PRO1") (pin "D50") (pinfunction "D50_D50") (pintype "bidirectional"))
    )
    (net (code "107") (name "unconnected-(MEGA2560PRO1-PadD51)") (class "Default")
      (node (ref "MEGA2560PRO1") (pin "D51") (pinfunction "D51_D51") (pintype "bidirectional"))
    )
    (net (code "108") (name "unconnected-(MEGA2560PRO1-PadD52)") (class "Default")
      (node (ref "MEGA2560PRO1") (pin "D52") (pinfunction "D52_D52") (pintype "bidirectional"))
    )
    (net (code "109") (name "unconnected-(MEGA2560PRO1-PadD53)") (class "Default")
      (node (ref "MEGA2560PRO1") (pin "D53") (pinfunction "D53_D53") (pintype "bidirectional"))
    )
    (net (code "110") (name "unconnected-(MEGA2560PRO1-PadRX)") (class "Default")
      (node (ref "MEGA2560PRO1") (pin "RX") (pinfunction "RX_RX") (pintype "bidirectional"))
    )
    (net (code "111") (name "unconnected-(MEGA2560PRO1-PadTX)") (class "Default")
      (node (ref "MEGA2560PRO1") (pin "TX") (pinfunction "TX_TX") (pintype "bidirectional"))
    )
    (net (code "112") (name "unconnected-(VR1-CCW-Pad1)") (class "Default")
      (node (ref "VR1") (pin "1") (pinfunction "CCW_1") (pintype "passive"))
    )
  )
)
